# Circuit_Schematic.net
KiCad netlist of a schematic drawn in Altium Designer
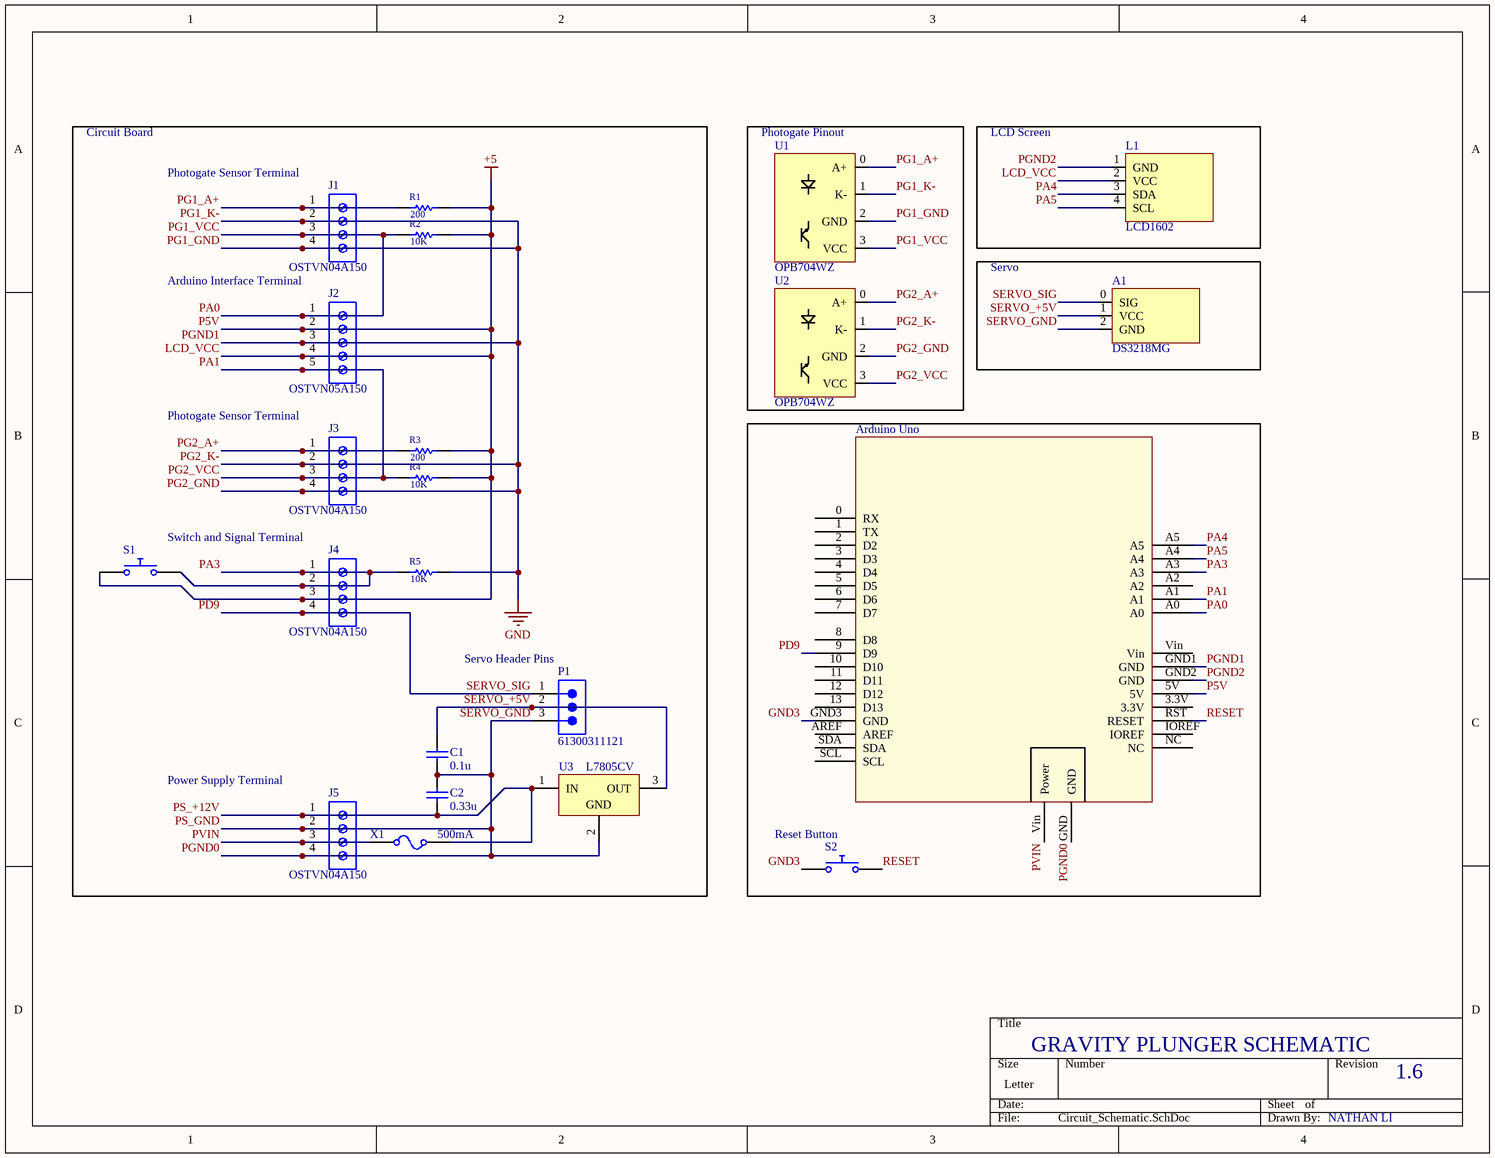
[diagram p0: Circuit_Schematic.SchDoc]

(export (version "E")
  (design (tool "Eeschema 10.0.6"))
  (components
    (comp (ref "A1")
      (value "DS3218MG")
      (description "270 Degree Servo")
      (libsource (lib "SchemLib") (part "DS3218MG"))
    )
    (comp (ref "Arduino Uno")
      (value "~")
      (footprint "uno:ARDUINO UNO")
      (libsource (lib "arduino") (part "ARDUINO UNO"))
    )
    (comp (ref "C1")
      (value "0.1u")
      (description "Capacitor")
      (libsource (lib "Simulation Generic Components") (part "Capacitor"))
    )
    (comp (ref "C2")
      (value "0.33u")
      (description "Capacitor")
      (libsource (lib "Simulation Generic Components") (part "Capacitor"))
    )
    (comp (ref "J1")
      (value "OSTVN04A150")
      (footprint "691709710304")
      (fields (field (name "VOLTAGE") "300V"))
      (libsource (lib "Altium Content Vault") (part "TBL - 1R - 04P - Screw"))
    )
    (comp (ref "J2")
      (value "OSTVN05A150")
      (footprint "691127700005B")
      (fields (field (name "VOLTAGE") "300V"))
      (libsource (lib "Altium Content Vault") (part "TBL - 1R - 05P - Screw"))
    )
    (comp (ref "J3")
      (value "OSTVN04A150")
      (footprint "691709710304")
      (fields (field (name "VOLTAGE") "300V"))
      (libsource (lib "Altium Content Vault") (part "TBL - 1R - 04P - Screw"))
    )
    (comp (ref "J4")
      (value "OSTVN04A150")
      (footprint "691709710304")
      (fields (field (name "VOLTAGE") "300V"))
      (libsource (lib "Altium Content Vault") (part "TBL - 1R - 04P - Screw"))
    )
    (comp (ref "J5")
      (value "OSTVN04A150")
      (footprint "691709710304")
      (fields (field (name "VOLTAGE") "300V"))
      (libsource (lib "Altium Content Vault") (part "TBL - 1R - 04P - Screw"))
    )
    (comp (ref "L1")
      (value "LCD1602")
      (description "Liquid I2C LCD 16x2 Display")
      (libsource (lib "SchemLib") (part "LCD 16x2"))
    )
    (comp (ref "P1")
      (value "61300311121")
      (footprint "61300311121")
      (libsource (lib "Altium Content Vault") (part "Header_Male_1R_03P"))
    )
    (comp (ref "R1")
      (value "200")
      (description "Resistor")
      (libsource (lib "Simulation Generic Components") (part "Resistor"))
    )
    (comp (ref "R2")
      (value "10K")
      (description "Resistor")
      (libsource (lib "Simulation Generic Components") (part "Resistor"))
    )
    (comp (ref "R3")
      (value "200")
      (description "Resistor")
      (libsource (lib "Simulation Generic Components") (part "Resistor"))
    )
    (comp (ref "R4")
      (value "10K")
      (description "Resistor")
      (libsource (lib "Simulation Generic Components") (part "Resistor"))
    )
    (comp (ref "R5")
      (value "10K")
      (description "Resistor")
      (libsource (lib "Simulation Generic Components") (part "Resistor"))
    )
    (comp (ref "S1")
      (value "Push Button Normally Opened")
      (libsource (lib "Simulation Generic Components") (part "Push Button NO"))
    )
    (comp (ref "S2")
      (value "Push Button Normally Opened")
      (libsource (lib "Simulation Generic Components") (part "Push Button NO"))
    )
    (comp (ref "U1") (value "OPB704WZ") (libsource (lib "SchemLib") (part "OPB704WZ")))
    (comp (ref "U2") (value "OPB704WZ") (libsource (lib "SchemLib") (part "OPB704WZ")))
    (comp (ref "U3")
      (value "L7805CV")
      (footprint "TO220")
      (description "Positive Voltage Regulator, 5V, 3-Pin TO-220")
      (libsource (lib "Altium Content Vault") (part "PM-REG-L4940-SIL3"))
    )
    (comp (ref "X1")
      (value "Fuse")
      (fields (field (name "CURRENT") "500mA"))
      (libsource (lib "Simulation Generic Components") (part "Fuse"))
    )
  )
  (nets
    (net (code "1") (name "+5") (class "Default")
      (node (ref "Arduino Uno") (pin "5V") (pinfunction "5V_5V") (pintype "passive"))
      (node (ref "J2") (pin "2") (pinfunction "2_2") (pintype "passive"))
      (node (ref "J2") (pin "4") (pinfunction "4_4") (pintype "passive"))
      (node (ref "J4") (pin "3") (pinfunction "3_3") (pintype "passive"))
      (node (ref "L1") (pin "2") (pinfunction "VCC_2") (pintype "passive"))
      (node (ref "R1") (pin "2") (pinfunction "2_2") (pintype "passive"))
      (node (ref "R2") (pin "2") (pinfunction "2_2") (pintype "passive"))
      (node (ref "R3") (pin "2") (pinfunction "2_2") (pintype "passive"))
      (node (ref "R4") (pin "2") (pinfunction "2_2") (pintype "passive"))
      (node (ref "S1") (pin "1") (pinfunction "1_1") (pintype "passive"))
    )
    (net (code "2") (name "/GND3") (class "Default")
      (node (ref "Arduino Uno") (pin "GND3") (pinfunction "GND_GND3") (pintype "passive"))
      (node (ref "S2") (pin "1") (pinfunction "1_1") (pintype "passive"))
    )
    (net (code "3") (name "/PA0") (class "Default")
      (node (ref "Arduino Uno") (pin "A0") (pinfunction "A0_A0") (pintype "passive"))
      (node (ref "J1") (pin "3") (pinfunction "3_3") (pintype "passive"))
      (node (ref "J2") (pin "1") (pinfunction "1_1") (pintype "passive"))
      (node (ref "R2") (pin "1") (pinfunction "1_1") (pintype "passive"))
      (node (ref "U1") (pin "3") (pinfunction "VCC_3") (pintype "passive"))
    )
    (net (code "4") (name "/PA1") (class "Default")
      (node (ref "Arduino Uno") (pin "A1") (pinfunction "A1_A1") (pintype "passive"))
      (node (ref "J2") (pin "5") (pinfunction "5_5") (pintype "passive"))
      (node (ref "J3") (pin "3") (pinfunction "3_3") (pintype "passive"))
      (node (ref "R4") (pin "1") (pinfunction "1_1") (pintype "passive"))
      (node (ref "U2") (pin "3") (pinfunction "VCC_3") (pintype "passive"))
    )
    (net (code "5") (name "/PA3") (class "Default")
      (node (ref "Arduino Uno") (pin "A3") (pinfunction "A3_A3") (pintype "passive"))
      (node (ref "J4") (pin "1") (pinfunction "1_1") (pintype "passive"))
      (node (ref "J4") (pin "2") (pinfunction "2_2") (pintype "passive"))
      (node (ref "R5") (pin "1") (pinfunction "1_1") (pintype "passive"))
      (node (ref "S1") (pin "2") (pinfunction "2_2") (pintype "passive"))
    )
    (net (code "6") (name "/PA4") (class "Default")
      (node (ref "Arduino Uno") (pin "A5") (pinfunction "A5_A5") (pintype "passive"))
      (node (ref "L1") (pin "3") (pinfunction "SDA_3") (pintype "passive"))
    )
    (net (code "7") (name "/PA5") (class "Default")
      (node (ref "Arduino Uno") (pin "A4") (pinfunction "A4_A4") (pintype "passive"))
      (node (ref "L1") (pin "4") (pinfunction "SCL_4") (pintype "passive"))
    )
    (net (code "8") (name "/PD9") (class "Default")
      (node (ref "A1") (pin "0") (pinfunction "SIG_0") (pintype "passive"))
      (node (ref "Arduino Uno") (pin "9") (pinfunction "D9_9") (pintype "passive"))
      (node (ref "J4") (pin "4") (pinfunction "4_4") (pintype "passive"))
      (node (ref "P1") (pin "1") (pinfunction "1_1") (pintype "passive"))
    )
    (net (code "9") (name "/PG1_A+") (class "Default")
      (node (ref "J1") (pin "1") (pinfunction "1_1") (pintype "passive"))
      (node (ref "R1") (pin "1") (pinfunction "1_1") (pintype "passive"))
      (node (ref "U1") (pin "0") (pinfunction "A+_0") (pintype "passive"))
    )
    (net (code "10") (name "/PG2_A+") (class "Default")
      (node (ref "J3") (pin "1") (pinfunction "1_1") (pintype "passive"))
      (node (ref "R3") (pin "1") (pinfunction "1_1") (pintype "passive"))
      (node (ref "U2") (pin "0") (pinfunction "A+_0") (pintype "passive"))
    )
    (net (code "11") (name "/PGND0") (class "Default")
      (node (ref "A1") (pin "2") (pinfunction "GND_2") (pintype "passive"))
      (node (ref "Arduino Uno") (pin "GND") (pinfunction "GND_GND") (pintype "passive"))
      (node (ref "C1") (pin "2") (pinfunction "2_2") (pintype "passive"))
      (node (ref "C2") (pin "2") (pinfunction "2_2") (pintype "passive"))
      (node (ref "J5") (pin "2") (pinfunction "2_2") (pintype "passive"))
      (node (ref "J5") (pin "4") (pinfunction "4_4") (pintype "passive"))
      (node (ref "P1") (pin "3") (pinfunction "3_3") (pintype "passive"))
      (node (ref "U3") (pin "2") (pinfunction "GND_2") (pintype "power_in"))
    )
    (net (code "12") (name "/PGND2") (class "Default")
      (node (ref "Arduino Uno") (pin "GND2") (pinfunction "GND_GND2") (pintype "passive"))
      (node (ref "L1") (pin "1") (pinfunction "GND_1") (pintype "passive"))
    )
    (net (code "13") (name "/PS_+12V") (class "Default")
      (node (ref "C2") (pin "1") (pinfunction "1_1") (pintype "passive"))
      (node (ref "J5") (pin "1") (pinfunction "1_1") (pintype "passive"))
      (node (ref "U3") (pin "1") (pinfunction "IN_1") (pintype "power_in"))
      (node (ref "X1") (pin "2") (pinfunction "2_2") (pintype "passive"))
    )
    (net (code "14") (name "/PVIN") (class "Default")
      (node (ref "Arduino Uno") (pin "Vin") (pinfunction "Power_Vin") (pintype "passive"))
      (node (ref "J5") (pin "3") (pinfunction "3_3") (pintype "passive"))
      (node (ref "X1") (pin "1") (pinfunction "1_1") (pintype "passive"))
    )
    (net (code "15") (name "/RESET") (class "Default")
      (node (ref "Arduino Uno") (pin "RST") (pinfunction "RESET_RST") (pintype "passive"))
      (node (ref "S2") (pin "2") (pinfunction "2_2") (pintype "passive"))
    )
    (net (code "16") (name "/SERVO_+5V") (class "Default")
      (node (ref "A1") (pin "1") (pinfunction "VCC_1") (pintype "passive"))
      (node (ref "C1") (pin "1") (pinfunction "1_1") (pintype "passive"))
      (node (ref "P1") (pin "2") (pinfunction "2_2") (pintype "passive"))
      (node (ref "U3") (pin "3") (pinfunction "OUT_3") (pintype "power_in"))
    )
    (net (code "17") (name "GND") (class "Default")
      (node (ref "Arduino Uno") (pin "GND1") (pinfunction "GND_GND1") (pintype "passive"))
      (node (ref "J1") (pin "2") (pinfunction "2_2") (pintype "passive"))
      (node (ref "J1") (pin "4") (pinfunction "4_4") (pintype "passive"))
      (node (ref "J2") (pin "3") (pinfunction "3_3") (pintype "passive"))
      (node (ref "J3") (pin "2") (pinfunction "2_2") (pintype "passive"))
      (node (ref "J3") (pin "4") (pinfunction "4_4") (pintype "passive"))
      (node (ref "R5") (pin "2") (pinfunction "2_2") (pintype "passive"))
      (node (ref "U1") (pin "1") (pinfunction "K-_1") (pintype "passive"))
      (node (ref "U1") (pin "2") (pinfunction "GND_2") (pintype "passive"))
      (node (ref "U2") (pin "1") (pinfunction "K-_1") (pintype "passive"))
      (node (ref "U2") (pin "2") (pinfunction "GND_2") (pintype "passive"))
    )
    (net (code "18") (name "unconnected-(Arduino Uno-D2-Pad2)") (class "Default")
      (node (ref "Arduino Uno") (pin "2") (pinfunction "D2_2") (pintype "passive"))
    )
    (net (code "19") (name "unconnected-(Arduino Uno-D3-Pad3)") (class "Default")
      (node (ref "Arduino Uno") (pin "3") (pinfunction "D3_3") (pintype "passive"))
    )
    (net (code "20") (name "unconnected-(Arduino Uno-D4-Pad4)") (class "Default")
      (node (ref "Arduino Uno") (pin "4") (pinfunction "D4_4") (pintype "passive"))
    )
    (net (code "21") (name "unconnected-(Arduino Uno-D5-Pad5)") (class "Default")
      (node (ref "Arduino Uno") (pin "5") (pinfunction "D5_5") (pintype "passive"))
    )
    (net (code "22") (name "unconnected-(Arduino Uno-D6-Pad6)") (class "Default")
      (node (ref "Arduino Uno") (pin "6") (pinfunction "D6_6") (pintype "passive"))
    )
    (net (code "23") (name "unconnected-(Arduino Uno-D7-Pad7)") (class "Default")
      (node (ref "Arduino Uno") (pin "7") (pinfunction "D7_7") (pintype "passive"))
    )
    (net (code "24") (name "unconnected-(Arduino Uno-D8-Pad8)") (class "Default")
      (node (ref "Arduino Uno") (pin "8") (pinfunction "D8_8") (pintype "passive"))
    )
    (net (code "25") (name "unconnected-(Arduino Uno-D10-Pad10)") (class "Default")
      (node (ref "Arduino Uno") (pin "10") (pinfunction "D10_10") (pintype "passive"))
    )
    (net (code "26") (name "unconnected-(Arduino Uno-D11-Pad11)") (class "Default")
      (node (ref "Arduino Uno") (pin "11") (pinfunction "D11_11") (pintype "passive"))
    )
    (net (code "27") (name "unconnected-(Arduino Uno-D12-Pad12)") (class "Default")
      (node (ref "Arduino Uno") (pin "12") (pinfunction "D12_12") (pintype "passive"))
    )
    (net (code "28") (name "unconnected-(Arduino Uno-D13-Pad13)") (class "Default")
      (node (ref "Arduino Uno") (pin "13") (pinfunction "D13_13") (pintype "passive"))
    )
    (net (code "29") (name "unconnected-(Arduino Uno-Pad3.3V)") (class "Default")
      (node (ref "Arduino Uno") (pin "3.3V") (pinfunction "3.3V_3.3V") (pintype "passive"))
    )
    (net (code "30") (name "unconnected-(Arduino Uno-PadA2)") (class "Default")
      (node (ref "Arduino Uno") (pin "A2") (pinfunction "A2_A2") (pintype "passive"))
    )
    (net (code "31") (name "unconnected-(Arduino Uno-PadAREF)") (class "Default")
      (node (ref "Arduino Uno") (pin "AREF") (pinfunction "AREF_AREF") (pintype "passive"))
    )
    (net (code "32") (name "unconnected-(Arduino Uno-PadIOREF)") (class "Default")
      (node (ref "Arduino Uno") (pin "IOREF") (pinfunction "IOREF_IOREF") (pintype "passive"))
    )
    (net (code "33") (name "unconnected-(Arduino Uno-PadNC)") (class "Default")
      (node (ref "Arduino Uno") (pin "NC") (pinfunction "NC_NC") (pintype "passive"))
    )
    (net (code "34") (name "unconnected-(Arduino Uno-PadSCL)") (class "Default")
      (node (ref "Arduino Uno") (pin "SCL") (pinfunction "SCL_SCL") (pintype "passive"))
    )
    (net (code "35") (name "unconnected-(Arduino Uno-PadSDA)") (class "Default")
      (node (ref "Arduino Uno") (pin "SDA") (pinfunction "SDA_SDA") (pintype "passive"))
    )
    (net (code "36") (name "unconnected-(Arduino Uno-PadVin)") (class "Default")
      (node (ref "Arduino Uno") (pin "Vin") (pinfunction "Vin_Vin") (pintype "passive"))
    )
    (net (code "37") (name "unconnected-(Arduino Uno-RX-Pad0)") (class "Default")
      (node (ref "Arduino Uno") (pin "0") (pinfunction "RX_0") (pintype "passive"))
    )
    (net (code "38") (name "unconnected-(Arduino Uno-TX-Pad1)") (class "Default")
      (node (ref "Arduino Uno") (pin "1") (pinfunction "TX_1") (pintype "passive"))
    )
  )
)
